# avrshift-irlml2.net
KiCad netlist of a schematic drawn in EAGLE
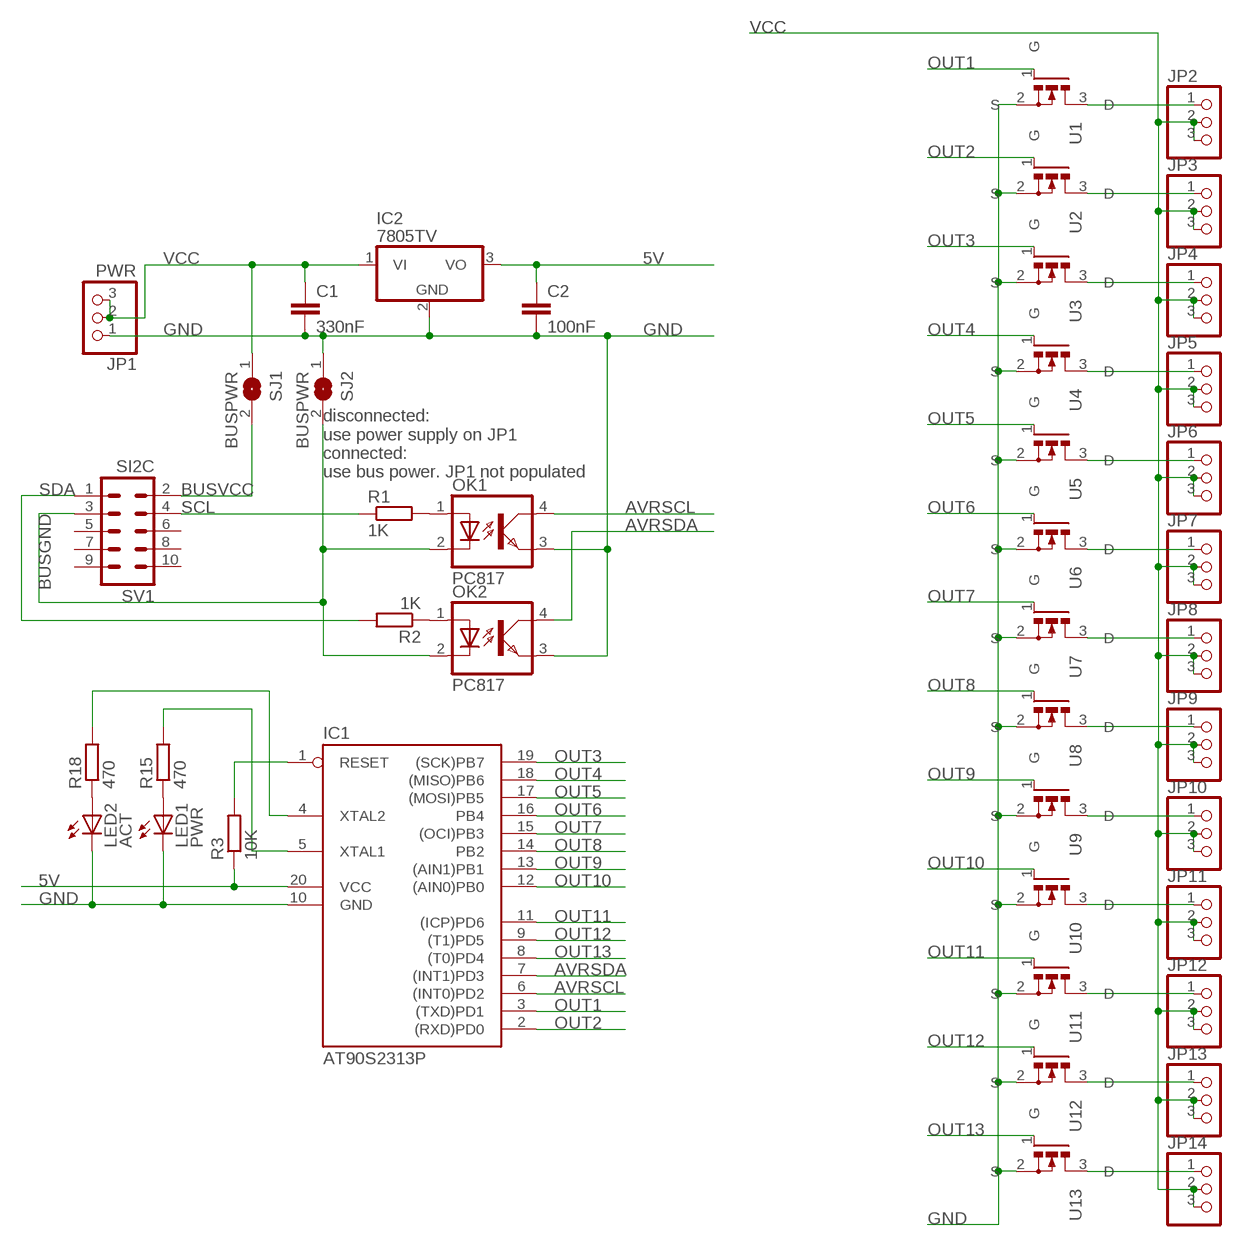
[diagram p0: schematic, sheet 1]

(export (version "E")
  (design (tool "Eeschema 10.0.6"))
  (components
    (comp (ref "C1")
      (value "330nF")
      (footprint "eagle-import:C0805")
      (libsource (lib "eagle-import") (part "C-EUC0805"))
    )
    (comp (ref "C2")
      (value "100nF")
      (footprint "eagle-import:C0805")
      (libsource (lib "eagle-import") (part "C-EUC0805"))
    )
    (comp (ref "IC1")
      (value "AT90S2313P")
      (footprint "eagle-import:DIL20")
      (libsource (lib "eagle-import") (part "AT90S2313P"))
    )
    (comp (ref "IC2")
      (value "7805TV")
      (footprint "eagle-import:TO220V")
      (libsource (lib "eagle-import") (part "78TV05"))
    )
    (comp (ref "JP1")
      (value "PWR")
      (footprint "eagle-import:1X03")
      (libsource (lib "eagle-import") (part "PINHD-1X3"))
    )
    (comp (ref "JP2")
      (value "PINHD-1X3")
      (footprint "eagle-import:1X03")
      (libsource (lib "eagle-import") (part "PINHD-1X3"))
    )
    (comp (ref "JP3")
      (value "PINHD-1X3")
      (footprint "eagle-import:1X03")
      (libsource (lib "eagle-import") (part "PINHD-1X3"))
    )
    (comp (ref "JP4")
      (value "PINHD-1X3")
      (footprint "eagle-import:1X03")
      (libsource (lib "eagle-import") (part "PINHD-1X3"))
    )
    (comp (ref "JP5")
      (value "PINHD-1X3")
      (footprint "eagle-import:1X03")
      (libsource (lib "eagle-import") (part "PINHD-1X3"))
    )
    (comp (ref "JP6")
      (value "PINHD-1X3")
      (footprint "eagle-import:1X03")
      (libsource (lib "eagle-import") (part "PINHD-1X3"))
    )
    (comp (ref "JP7")
      (value "PINHD-1X3")
      (footprint "eagle-import:1X03")
      (libsource (lib "eagle-import") (part "PINHD-1X3"))
    )
    (comp (ref "JP8")
      (value "PINHD-1X3")
      (footprint "eagle-import:1X03")
      (libsource (lib "eagle-import") (part "PINHD-1X3"))
    )
    (comp (ref "JP9")
      (value "PINHD-1X3")
      (footprint "eagle-import:1X03")
      (libsource (lib "eagle-import") (part "PINHD-1X3"))
    )
    (comp (ref "JP10")
      (value "PINHD-1X3")
      (footprint "eagle-import:1X03")
      (libsource (lib "eagle-import") (part "PINHD-1X3"))
    )
    (comp (ref "JP11")
      (value "PINHD-1X3")
      (footprint "eagle-import:1X03")
      (libsource (lib "eagle-import") (part "PINHD-1X3"))
    )
    (comp (ref "JP12")
      (value "PINHD-1X3")
      (footprint "eagle-import:1X03")
      (libsource (lib "eagle-import") (part "PINHD-1X3"))
    )
    (comp (ref "JP13")
      (value "PINHD-1X3")
      (footprint "eagle-import:1X03")
      (libsource (lib "eagle-import") (part "PINHD-1X3"))
    )
    (comp (ref "JP14")
      (value "PINHD-1X3")
      (footprint "eagle-import:1X03")
      (libsource (lib "eagle-import") (part "PINHD-1X3"))
    )
    (comp (ref "LED1")
      (value "PWR")
      (footprint "eagle-import:LED3MM")
      (libsource (lib "eagle-import") (part "LED3MM"))
    )
    (comp (ref "LED2")
      (value "ACT")
      (footprint "eagle-import:LED3MM")
      (libsource (lib "eagle-import") (part "LED3MM"))
    )
    (comp (ref "OK1")
      (value "PC817")
      (footprint "eagle-import:DIL04")
      (fields (field (name "MPN") "PC817X4J000F"))
      (libsource (lib "eagle-import") (part "PC817"))
    )
    (comp (ref "OK2")
      (value "PC817")
      (footprint "eagle-import:DIL04")
      (fields (field (name "MPN") "PC817X4J000F"))
      (libsource (lib "eagle-import") (part "PC817"))
    )
    (comp (ref "R1")
      (value "1K")
      (footprint "eagle-import:0207_2V")
      (libsource (lib "eagle-import") (part "R-EU_0207/2V"))
    )
    (comp (ref "R2")
      (value "1K")
      (footprint "eagle-import:0207_2V")
      (libsource (lib "eagle-import") (part "R-EU_0207/2V"))
    )
    (comp (ref "R3")
      (value "10K")
      (footprint "eagle-import:R0805")
      (libsource (lib "eagle-import") (part "R-EU_R0805"))
    )
    (comp (ref "R15")
      (value "470")
      (footprint "eagle-import:0207_2V")
      (libsource (lib "eagle-import") (part "R-EU_0207/2V"))
    )
    (comp (ref "R18")
      (value "470")
      (footprint "eagle-import:0207_2V")
      (libsource (lib "eagle-import") (part "R-EU_0207/2V"))
    )
    (comp (ref "SJ1")
      (value "BUSPWR")
      (footprint "eagle-import:SJ")
      (libsource (lib "eagle-import") (part "SJ"))
    )
    (comp (ref "SJ2")
      (value "BUSPWR")
      (footprint "eagle-import:SJ")
      (libsource (lib "eagle-import") (part "SJ"))
    )
    (comp (ref "SV1")
      (value "SI2C")
      (footprint "eagle-import:ML10")
      (libsource (lib "eagle-import") (part "ML10"))
    )
    (comp (ref "U1")
      (value "IRFML8244TRPBF")
      (footprint "eagle-import:SOT95P240X112-3N")
      (libsource (lib "eagle-import") (part "IRFML8244TRPBF"))
    )
    (comp (ref "U2")
      (value "IRFML8244TRPBF")
      (footprint "eagle-import:SOT95P240X112-3N")
      (libsource (lib "eagle-import") (part "IRFML8244TRPBF"))
    )
    (comp (ref "U3")
      (value "IRFML8244TRPBF")
      (footprint "eagle-import:SOT95P240X112-3N")
      (libsource (lib "eagle-import") (part "IRFML8244TRPBF"))
    )
    (comp (ref "U4")
      (value "IRFML8244TRPBF")
      (footprint "eagle-import:SOT95P240X112-3N")
      (libsource (lib "eagle-import") (part "IRFML8244TRPBF"))
    )
    (comp (ref "U5")
      (value "IRFML8244TRPBF")
      (footprint "eagle-import:SOT95P240X112-3N")
      (libsource (lib "eagle-import") (part "IRFML8244TRPBF"))
    )
    (comp (ref "U6")
      (value "IRFML8244TRPBF")
      (footprint "eagle-import:SOT95P240X112-3N")
      (libsource (lib "eagle-import") (part "IRFML8244TRPBF"))
    )
    (comp (ref "U7")
      (value "IRFML8244TRPBF")
      (footprint "eagle-import:SOT95P240X112-3N")
      (libsource (lib "eagle-import") (part "IRFML8244TRPBF"))
    )
    (comp (ref "U8")
      (value "IRFML8244TRPBF")
      (footprint "eagle-import:SOT95P240X112-3N")
      (libsource (lib "eagle-import") (part "IRFML8244TRPBF"))
    )
    (comp (ref "U9")
      (value "IRFML8244TRPBF")
      (footprint "eagle-import:SOT95P240X112-3N")
      (libsource (lib "eagle-import") (part "IRFML8244TRPBF"))
    )
    (comp (ref "U10")
      (value "IRFML8244TRPBF")
      (footprint "eagle-import:SOT95P240X112-3N")
      (libsource (lib "eagle-import") (part "IRFML8244TRPBF"))
    )
    (comp (ref "U11")
      (value "IRFML8244TRPBF")
      (footprint "eagle-import:SOT95P240X112-3N")
      (libsource (lib "eagle-import") (part "IRFML8244TRPBF"))
    )
    (comp (ref "U12")
      (value "IRFML8244TRPBF")
      (footprint "eagle-import:SOT95P240X112-3N")
      (libsource (lib "eagle-import") (part "IRFML8244TRPBF"))
    )
    (comp (ref "U13")
      (value "IRFML8244TRPBF")
      (footprint "eagle-import:SOT95P240X112-3N")
      (libsource (lib "eagle-import") (part "IRFML8244TRPBF"))
    )
  )
  (nets
    (net (code "1") (name "/5V") (class "Default")
      (node (ref "C2") (pin "1") (pinfunction "1_1") (pintype "passive"))
      (node (ref "IC1") (pin "20") (pinfunction "VCC_20") (pintype "power_in"))
      (node (ref "IC2") (pin "3") (pinfunction "VO_3") (pintype "passive"))
      (node (ref "R3") (pin "1") (pinfunction "1_1") (pintype "passive"))
    )
    (net (code "2") (name "/AVRSCL") (class "Default")
      (node (ref "IC1") (pin "6") (pinfunction "(INT0)PD2_6") (pintype "bidirectional"))
      (node (ref "OK1") (pin "4") (pinfunction "COL_4") (pintype "passive"))
    )
    (net (code "3") (name "/AVRSDA") (class "Default")
      (node (ref "IC1") (pin "7") (pinfunction "(INT1)PD3_7") (pintype "bidirectional"))
      (node (ref "OK2") (pin "4") (pinfunction "COL_4") (pintype "passive"))
    )
    (net (code "4") (name "/BUSGND") (class "Default")
      (node (ref "OK1") (pin "2") (pinfunction "C_2") (pintype "passive"))
      (node (ref "OK2") (pin "2") (pinfunction "C_2") (pintype "passive"))
      (node (ref "SJ2") (pin "2") (pinfunction "2_2") (pintype "passive"))
      (node (ref "SV1") (pin "3") (pinfunction "3_3") (pintype "passive"))
    )
    (net (code "5") (name "/BUSVCC") (class "Default")
      (node (ref "SJ1") (pin "2") (pinfunction "2_2") (pintype "passive"))
      (node (ref "SV1") (pin "2") (pinfunction "2_2") (pintype "passive"))
    )
    (net (code "6") (name "/GND") (class "Default")
      (node (ref "C1") (pin "2") (pinfunction "2_2") (pintype "passive"))
      (node (ref "C2") (pin "2") (pinfunction "2_2") (pintype "passive"))
      (node (ref "IC1") (pin "10") (pinfunction "GND_10") (pintype "power_in"))
      (node (ref "IC2") (pin "2") (pinfunction "GND_2") (pintype "passive"))
      (node (ref "JP1") (pin "1") (pinfunction "1_1") (pintype "passive"))
      (node (ref "LED1") (pin "K") (pinfunction "C_K") (pintype "passive"))
      (node (ref "LED2") (pin "K") (pinfunction "C_K") (pintype "passive"))
      (node (ref "OK1") (pin "3") (pinfunction "EMIT_3") (pintype "passive"))
      (node (ref "OK2") (pin "3") (pinfunction "EMIT_3") (pintype "passive"))
      (node (ref "SJ2") (pin "1") (pinfunction "1_1") (pintype "passive"))
      (node (ref "U1") (pin "2") (pinfunction "S_2") (pintype "passive"))
      (node (ref "U10") (pin "2") (pinfunction "S_2") (pintype "passive"))
      (node (ref "U11") (pin "2") (pinfunction "S_2") (pintype "passive"))
      (node (ref "U12") (pin "2") (pinfunction "S_2") (pintype "passive"))
      (node (ref "U13") (pin "2") (pinfunction "S_2") (pintype "passive"))
      (node (ref "U2") (pin "2") (pinfunction "S_2") (pintype "passive"))
      (node (ref "U3") (pin "2") (pinfunction "S_2") (pintype "passive"))
      (node (ref "U4") (pin "2") (pinfunction "S_2") (pintype "passive"))
      (node (ref "U5") (pin "2") (pinfunction "S_2") (pintype "passive"))
      (node (ref "U6") (pin "2") (pinfunction "S_2") (pintype "passive"))
      (node (ref "U7") (pin "2") (pinfunction "S_2") (pintype "passive"))
      (node (ref "U8") (pin "2") (pinfunction "S_2") (pintype "passive"))
      (node (ref "U9") (pin "2") (pinfunction "S_2") (pintype "passive"))
    )
    (net (code "7") (name "/OUT1") (class "Default")
      (node (ref "IC1") (pin "3") (pinfunction "(TXD)PD1_3") (pintype "bidirectional"))
      (node (ref "U1") (pin "1") (pinfunction "G_1") (pintype "input"))
    )
    (net (code "8") (name "/OUT2") (class "Default")
      (node (ref "IC1") (pin "2") (pinfunction "(RXD)PD0_2") (pintype "bidirectional"))
      (node (ref "U2") (pin "1") (pinfunction "G_1") (pintype "input"))
    )
    (net (code "9") (name "/OUT3") (class "Default")
      (node (ref "IC1") (pin "19") (pinfunction "(SCK)PB7_19") (pintype "bidirectional"))
      (node (ref "U3") (pin "1") (pinfunction "G_1") (pintype "input"))
    )
    (net (code "10") (name "/OUT4") (class "Default")
      (node (ref "IC1") (pin "18") (pinfunction "(MISO)PB6_18") (pintype "bidirectional"))
      (node (ref "U4") (pin "1") (pinfunction "G_1") (pintype "input"))
    )
    (net (code "11") (name "/OUT5") (class "Default")
      (node (ref "IC1") (pin "17") (pinfunction "(MOSI)PB5_17") (pintype "bidirectional"))
      (node (ref "U5") (pin "1") (pinfunction "G_1") (pintype "input"))
    )
    (net (code "12") (name "/OUT6") (class "Default")
      (node (ref "IC1") (pin "16") (pinfunction "PB4_16") (pintype "bidirectional"))
      (node (ref "U6") (pin "1") (pinfunction "G_1") (pintype "input"))
    )
    (net (code "13") (name "/OUT7") (class "Default")
      (node (ref "IC1") (pin "15") (pinfunction "(OCI)PB3_15") (pintype "bidirectional"))
      (node (ref "U7") (pin "1") (pinfunction "G_1") (pintype "input"))
    )
    (net (code "14") (name "/OUT8") (class "Default")
      (node (ref "IC1") (pin "14") (pinfunction "PB2_14") (pintype "bidirectional"))
      (node (ref "U8") (pin "1") (pinfunction "G_1") (pintype "input"))
    )
    (net (code "15") (name "/OUT9") (class "Default")
      (node (ref "IC1") (pin "13") (pinfunction "(AIN1)PB1_13") (pintype "bidirectional"))
      (node (ref "U9") (pin "1") (pinfunction "G_1") (pintype "input"))
    )
    (net (code "16") (name "/OUT10") (class "Default")
      (node (ref "IC1") (pin "12") (pinfunction "(AIN0)PB0_12") (pintype "bidirectional"))
      (node (ref "U10") (pin "1") (pinfunction "G_1") (pintype "input"))
    )
    (net (code "17") (name "/OUT11") (class "Default")
      (node (ref "IC1") (pin "11") (pinfunction "(ICP)PD6_11") (pintype "bidirectional"))
      (node (ref "U11") (pin "1") (pinfunction "G_1") (pintype "input"))
    )
    (net (code "18") (name "/OUT12") (class "Default")
      (node (ref "IC1") (pin "9") (pinfunction "(T1)PD5_9") (pintype "bidirectional"))
      (node (ref "U12") (pin "1") (pinfunction "G_1") (pintype "input"))
    )
    (net (code "19") (name "/OUT13") (class "Default")
      (node (ref "IC1") (pin "8") (pinfunction "(T0)PD4_8") (pintype "bidirectional"))
      (node (ref "U13") (pin "1") (pinfunction "G_1") (pintype "input"))
    )
    (net (code "20") (name "/SCL") (class "Default")
      (node (ref "R1") (pin "1") (pinfunction "1_1") (pintype "passive"))
      (node (ref "SV1") (pin "4") (pinfunction "4_4") (pintype "passive"))
    )
    (net (code "21") (name "/SDA") (class "Default")
      (node (ref "R2") (pin "2") (pinfunction "2_2") (pintype "passive"))
      (node (ref "SV1") (pin "1") (pinfunction "1_1") (pintype "passive"))
    )
    (net (code "22") (name "/VCC") (class "Default")
      (node (ref "C1") (pin "1") (pinfunction "1_1") (pintype "passive"))
      (node (ref "IC2") (pin "1") (pinfunction "VI_1") (pintype "input"))
      (node (ref "JP1") (pin "2") (pinfunction "2_2") (pintype "passive"))
      (node (ref "JP1") (pin "3") (pinfunction "3_3") (pintype "passive"))
      (node (ref "JP10") (pin "2") (pinfunction "2_2") (pintype "passive"))
      (node (ref "JP10") (pin "3") (pinfunction "3_3") (pintype "passive"))
      (node (ref "JP11") (pin "2") (pinfunction "2_2") (pintype "passive"))
      (node (ref "JP11") (pin "3") (pinfunction "3_3") (pintype "passive"))
      (node (ref "JP12") (pin "2") (pinfunction "2_2") (pintype "passive"))
      (node (ref "JP12") (pin "3") (pinfunction "3_3") (pintype "passive"))
      (node (ref "JP13") (pin "2") (pinfunction "2_2") (pintype "passive"))
      (node (ref "JP13") (pin "3") (pinfunction "3_3") (pintype "passive"))
      (node (ref "JP14") (pin "2") (pinfunction "2_2") (pintype "passive"))
      (node (ref "JP14") (pin "3") (pinfunction "3_3") (pintype "passive"))
      (node (ref "JP2") (pin "2") (pinfunction "2_2") (pintype "passive"))
      (node (ref "JP2") (pin "3") (pinfunction "3_3") (pintype "passive"))
      (node (ref "JP3") (pin "2") (pinfunction "2_2") (pintype "passive"))
      (node (ref "JP3") (pin "3") (pinfunction "3_3") (pintype "passive"))
      (node (ref "JP4") (pin "2") (pinfunction "2_2") (pintype "passive"))
      (node (ref "JP4") (pin "3") (pinfunction "3_3") (pintype "passive"))
      (node (ref "JP5") (pin "2") (pinfunction "2_2") (pintype "passive"))
      (node (ref "JP5") (pin "3") (pinfunction "3_3") (pintype "passive"))
      (node (ref "JP6") (pin "2") (pinfunction "2_2") (pintype "passive"))
      (node (ref "JP6") (pin "3") (pinfunction "3_3") (pintype "passive"))
      (node (ref "JP7") (pin "2") (pinfunction "2_2") (pintype "passive"))
      (node (ref "JP7") (pin "3") (pinfunction "3_3") (pintype "passive"))
      (node (ref "JP8") (pin "2") (pinfunction "2_2") (pintype "passive"))
      (node (ref "JP8") (pin "3") (pinfunction "3_3") (pintype "passive"))
      (node (ref "JP9") (pin "2") (pinfunction "2_2") (pintype "passive"))
      (node (ref "JP9") (pin "3") (pinfunction "3_3") (pintype "passive"))
      (node (ref "SJ1") (pin "1") (pinfunction "1_1") (pintype "passive"))
    )
    (net (code "23") (name "Net-(IC1-RESET)") (class "Default")
      (node (ref "IC1") (pin "1") (pinfunction "RESET_1") (pintype "bidirectional"))
      (node (ref "R3") (pin "2") (pinfunction "2_2") (pintype "passive"))
    )
    (net (code "24") (name "Net-(IC1-XTAL1)") (class "Default")
      (node (ref "IC1") (pin "5") (pinfunction "XTAL1_5") (pintype "bidirectional"))
      (node (ref "R15") (pin "2") (pinfunction "2_2") (pintype "passive"))
    )
    (net (code "25") (name "Net-(IC1-XTAL2)") (class "Default")
      (node (ref "IC1") (pin "4") (pinfunction "XTAL2_4") (pintype "bidirectional"))
      (node (ref "R18") (pin "2") (pinfunction "2_2") (pintype "passive"))
    )
    (net (code "26") (name "Net-(LED1-PadA)") (class "Default")
      (node (ref "LED1") (pin "A") (pinfunction "A_A") (pintype "passive"))
      (node (ref "R15") (pin "1") (pinfunction "1_1") (pintype "passive"))
    )
    (net (code "27") (name "Net-(LED2-PadA)") (class "Default")
      (node (ref "LED2") (pin "A") (pinfunction "A_A") (pintype "passive"))
      (node (ref "R18") (pin "1") (pinfunction "1_1") (pintype "passive"))
    )
    (net (code "28") (name "Net-(OK1-A)") (class "Default")
      (node (ref "OK1") (pin "1") (pinfunction "A_1") (pintype "passive"))
      (node (ref "R1") (pin "2") (pinfunction "2_2") (pintype "passive"))
    )
    (net (code "29") (name "Net-(OK2-A)") (class "Default")
      (node (ref "OK2") (pin "1") (pinfunction "A_1") (pintype "passive"))
      (node (ref "R2") (pin "1") (pinfunction "1_1") (pintype "passive"))
    )
    (net (code "30") (name "Net-(U1-D)") (class "Default")
      (node (ref "JP2") (pin "1") (pinfunction "1_1") (pintype "passive"))
      (node (ref "U1") (pin "3") (pinfunction "D_3") (pintype "output"))
    )
    (net (code "31") (name "Net-(U2-D)") (class "Default")
      (node (ref "JP3") (pin "1") (pinfunction "1_1") (pintype "passive"))
      (node (ref "U2") (pin "3") (pinfunction "D_3") (pintype "output"))
    )
    (net (code "32") (name "Net-(U3-D)") (class "Default")
      (node (ref "JP4") (pin "1") (pinfunction "1_1") (pintype "passive"))
      (node (ref "U3") (pin "3") (pinfunction "D_3") (pintype "output"))
    )
    (net (code "33") (name "Net-(U4-D)") (class "Default")
      (node (ref "JP5") (pin "1") (pinfunction "1_1") (pintype "passive"))
      (node (ref "U4") (pin "3") (pinfunction "D_3") (pintype "output"))
    )
    (net (code "34") (name "Net-(U5-D)") (class "Default")
      (node (ref "JP6") (pin "1") (pinfunction "1_1") (pintype "passive"))
      (node (ref "U5") (pin "3") (pinfunction "D_3") (pintype "output"))
    )
    (net (code "35") (name "Net-(U6-D)") (class "Default")
      (node (ref "JP7") (pin "1") (pinfunction "1_1") (pintype "passive"))
      (node (ref "U6") (pin "3") (pinfunction "D_3") (pintype "output"))
    )
    (net (code "36") (name "Net-(U7-D)") (class "Default")
      (node (ref "JP8") (pin "1") (pinfunction "1_1") (pintype "passive"))
      (node (ref "U7") (pin "3") (pinfunction "D_3") (pintype "output"))
    )
    (net (code "37") (name "Net-(U8-D)") (class "Default")
      (node (ref "JP9") (pin "1") (pinfunction "1_1") (pintype "passive"))
      (node (ref "U8") (pin "3") (pinfunction "D_3") (pintype "output"))
    )
    (net (code "38") (name "Net-(U9-D)") (class "Default")
      (node (ref "JP10") (pin "1") (pinfunction "1_1") (pintype "passive"))
      (node (ref "U9") (pin "3") (pinfunction "D_3") (pintype "output"))
    )
    (net (code "39") (name "Net-(U10-D)") (class "Default")
      (node (ref "JP11") (pin "1") (pinfunction "1_1") (pintype "passive"))
      (node (ref "U10") (pin "3") (pinfunction "D_3") (pintype "output"))
    )
    (net (code "40") (name "Net-(U11-D)") (class "Default")
      (node (ref "JP12") (pin "1") (pinfunction "1_1") (pintype "passive"))
      (node (ref "U11") (pin "3") (pinfunction "D_3") (pintype "output"))
    )
    (net (code "41") (name "Net-(U12-D)") (class "Default")
      (node (ref "JP13") (pin "1") (pinfunction "1_1") (pintype "passive"))
      (node (ref "U12") (pin "3") (pinfunction "D_3") (pintype "output"))
    )
    (net (code "42") (name "Net-(U13-D)") (class "Default")
      (node (ref "JP14") (pin "1") (pinfunction "1_1") (pintype "passive"))
      (node (ref "U13") (pin "3") (pinfunction "D_3") (pintype "output"))
    )
    (net (code "43") (name "unconnected-(SV1-Pad5)") (class "Default")
      (node (ref "SV1") (pin "5") (pinfunction "5_5") (pintype "passive"))
    )
    (net (code "44") (name "unconnected-(SV1-Pad6)") (class "Default")
      (node (ref "SV1") (pin "6") (pinfunction "6_6") (pintype "passive"))
    )
    (net (code "45") (name "unconnected-(SV1-Pad7)") (class "Default")
      (node (ref "SV1") (pin "7") (pinfunction "7_7") (pintype "passive"))
    )
    (net (code "46") (name "unconnected-(SV1-Pad8)") (class "Default")
      (node (ref "SV1") (pin "8") (pinfunction "8_8") (pintype "passive"))
    )
    (net (code "47") (name "unconnected-(SV1-Pad9)") (class "Default")
      (node (ref "SV1") (pin "9") (pinfunction "9_9") (pintype "passive"))
    )
    (net (code "48") (name "unconnected-(SV1-Pad10)") (class "Default")
      (node (ref "SV1") (pin "10") (pinfunction "10_10") (pintype "passive"))
    )
  )
)
